# Alt_BRD_UPS_3_3V.net
KiCad netlist of a schematic drawn in Altium Designer
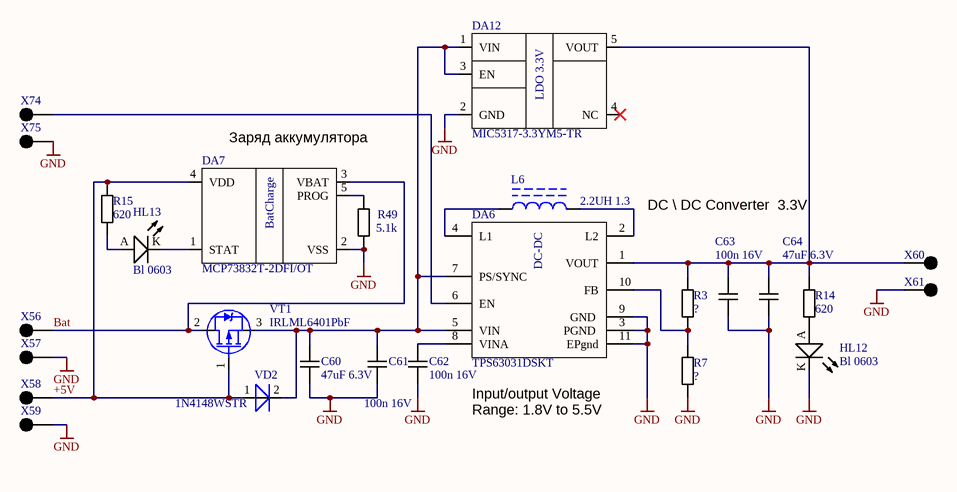
[diagram p0: Alt_BRD_UPS_3_3V.SchDoc]

(export (version "E")
  (design (tool "Eeschema 10.0.6"))
  (components
    (comp (ref "C60")
      (value "47uF 6.3V")
      (footprint "CapKemet1005(0402)")
      (description "CAP CER 47UF 6.3V X5R 0603")
      (fields
        (field (name "PART NUMBER") "GRM188R60J476ME15D")
        (field (name "DIGI-KEY PART NUMBER") "490-13247-1-ND")
      )
      (libsource (lib "SssAccesDatbase") (part "Cap"))
    )
    (comp (ref "C61")
      (value "100n 16V")
      (footprint "CapKemet1005(0402)")
      (description "Cap Cer 0.1uF 16V 1% C0G(NP0) MLCC")
      (fields
        (field (name "PART NUMBER") "CL05F104ZO5NNNC")
        (field (name "DIGI-KEY PART NUMBER") "1276-1004-1-ND")
      )
      (libsource (lib "SssAccesDatbase") (part "Cap"))
    )
    (comp (ref "C62")
      (value "100n 16V")
      (footprint "CapKemet1005(0402)")
      (description "Cap Cer 0.1uF 16V 1% C0G(NP0) MLCC")
      (fields
        (field (name "PART NUMBER") "CL05F104ZO5NNNC")
        (field (name "DIGI-KEY PART NUMBER") "1276-1004-1-ND")
      )
      (libsource (lib "SssAccesDatbase") (part "Cap"))
    )
    (comp (ref "C63")
      (value "100n 16V")
      (footprint "CapKemet1005(0402)")
      (description "Cap Cer 0.1uF 16V 1% C0G(NP0) MLCC")
      (fields
        (field (name "PART NUMBER") "CL05F104ZO5NNNC")
        (field (name "DIGI-KEY PART NUMBER") "1276-1004-1-ND")
      )
      (libsource (lib "SssAccesDatbase") (part "Cap"))
    )
    (comp (ref "C64")
      (value "47uF 6.3V")
      (footprint "CapKemet1005(0402)")
      (description "CAP CER 47UF 6.3V X5R 0603")
      (fields
        (field (name "PART NUMBER") "GRM188R60J476ME15D")
        (field (name "DIGI-KEY PART NUMBER") "490-13247-1-ND")
      )
      (libsource (lib "SssAccesDatbase") (part "Cap"))
    )
    (comp (ref "DA6")
      (value "TPS63031DSKT")
      (footprint "WSON-10")
      (description "IC REG BCK BST 3.3V 900MA 10SON")
      (fields (field (name "DIGI-KEY PART NUMBER") "296-23904-1-ND"))
      (libsource (lib "SssAccesDatbase") (part "TPS63031DSKR"))
    )
    (comp (ref "DA7")
      (value "MCP73832T-2DFI/OT")
      (footprint "SOT-23-5")
      (description "IC LI-ION/LI-POLY CTRLR SOT23-5")
      (fields (field (name "DIGI-KEY PART NUMBER") "MCP73832T-2DFI/OTCT-ND"))
      (libsource (lib "SssAccesDatbase") (part "MCP73832T-2DFI/OT"))
    )
    (comp (ref "DA12")
      (value "MIC5317-3.3YM5-TR")
      (footprint "SOT-23-OT5_N")
      (description "Linear Voltage Regulator IC 1 Output 150mA SOT-23-5")
      (fields (field (name "DIGI-KEY PART NUMBER") "MIC5317-3.3YM5-CT-ND"))
      (libsource (lib "SssAccesDatbase") (part "MIC5317-3.3YM5-TR"))
    )
    (comp (ref "HL12")
      (value "Bl 0603")
      (footprint "LED-0603-BLUE")
      (description "LED BLUE DIFFUSED 0603 SMD")
      (fields
        (field (name "PART NUMBER") "150060BS55040")
        (field (name "DIGI-KEY PART NUMBER") "732-12013-1-ND")
      )
      (libsource (lib "SssAccesDatbase") (part "LED_AK"))
    )
    (comp (ref "HL13")
      (value "Bl 0603")
      (footprint "LED-0603-BLUE")
      (description "LED BLUE DIFFUSED 0603 SMD")
      (fields
        (field (name "PART NUMBER") "150060BS55040")
        (field (name "DIGI-KEY PART NUMBER") "732-12013-1-ND")
      )
      (libsource (lib "SssAccesDatbase") (part "LED_AK"))
    )
    (comp (ref "L6")
      (value "2.2UH 1.3")
      (footprint "CDRH2D11")
      (description "FIXED IND 2.2UH 1.3A 120 MOHM")
      (fields
        (field (name "PART NUMBER") "CDRH2D11/HPNP-2R2NC")
        (field (name "DIGI-KEY PART NUMBER") "308-1578-1-ND")
        (field (name "PUBLISHER") "Altium Limited")
      )
      (libsource (lib "SssAccesDatbase") (part "Inductor ferrite"))
    )
    (comp (ref "R3")
      (value "?")
      (footprint "REZKemet 0402")
      (fields (field (name "PART NUMBER") "RESC1005(0402)"))
      (libsource (lib "SssAccesDatbase") (part "Resistor general"))
    )
    (comp (ref "R7")
      (value "?")
      (footprint "REZKemet 0402")
      (fields (field (name "PART NUMBER") "RESC1005(0402)"))
      (libsource (lib "SssAccesDatbase") (part "Resistor general"))
    )
    (comp (ref "R14")
      (value "620")
      (footprint "REZKemet 0402")
      (fields (field (name "PART NUMBER") "RESC1005(0402)"))
      (libsource (lib "SssAccesDatbase") (part "Resistor general"))
    )
    (comp (ref "R15")
      (value "620")
      (footprint "REZKemet 0402")
      (fields (field (name "PART NUMBER") "RESC1005(0402)"))
      (libsource (lib "SssAccesDatbase") (part "Resistor general"))
    )
    (comp (ref "R49")
      (value "5.1k")
      (footprint "REZKemet 0402")
      (description "RES SMD 5.1K OHM 1% 1/10W 0402")
      (fields
        (field (name "PART NUMBER") "RESC1005(0402)")
        (field (name "MANUFACTURER PART NUMBER") "ERJ-2RKF5101X")
      )
      (libsource (lib "") (part "Resistor general_1"))
    )
    (comp (ref "VD2")
      (value "1N4148WSTR")
      (footprint "SOD323")
      (description "DIODE GEN PURP 75V 300MA SOD323")
      (fields
        (field (name "DIGI-KEY PART NUMBER") "1655-1359-1-ND")
        (field (name "MANUFACTURER PART NUMBER") "?")
        (field (name "PUBLISHER") "Altium Limited")
      )
      (libsource (lib "SssAccesDatbase") (part "Diode"))
    )
    (comp (ref "VT1")
      (value "IRLML6401PbF")
      (footprint "SOT23-3N")
      (fields (field (name "DIGI-KEY PART NUMBER") "???"))
      (libsource (lib "SssAccesDatbase") (part "TRANS-P-Channel-GDS"))
    )
    (comp (ref "X56")
      (value "PLLS1.27-1-R")
      (footprint "PLLS1.27-1-R")
      (libsource (lib "SssAccesDatbase") (part "X1_1"))
    )
    (comp (ref "X57")
      (value "PLLS1.27-1-R")
      (footprint "PLLS1.27-1-R")
      (libsource (lib "SssAccesDatbase") (part "X1_1"))
    )
    (comp (ref "X58")
      (value "PLLS1.27-1-R")
      (footprint "PLLS1.27-1-R")
      (libsource (lib "SssAccesDatbase") (part "X1_1"))
    )
    (comp (ref "X59")
      (value "PLLS1.27-1-R")
      (footprint "PLLS1.27-1-R")
      (libsource (lib "SssAccesDatbase") (part "X1_1"))
    )
    (comp (ref "X60")
      (value "PLLS1.27-1-R")
      (footprint "PLLS1.27-1-R")
      (libsource (lib "SssAccesDatbase") (part "X1_1"))
    )
    (comp (ref "X61")
      (value "PLLS1.27-1-R")
      (footprint "PLLS1.27-1-R")
      (libsource (lib "SssAccesDatbase") (part "X1_1"))
    )
    (comp (ref "X74")
      (value "PLLS1.27-1-R")
      (footprint "PLLS1.27-1-R")
      (libsource (lib "SssAccesDatbase") (part "X1_1"))
    )
    (comp (ref "X75")
      (value "PLLS1.27-1-R")
      (footprint "PLLS1.27-1-R")
      (libsource (lib "SssAccesDatbase") (part "X1_1"))
    )
  )
  (nets
    (net (code "1") (name "/+5V") (class "Default")
      (node (ref "DA7") (pin "4") (pinfunction "VDD_4") (pintype "passive"))
      (node (ref "R15") (pin "2") (pinfunction "2_2") (pintype "passive"))
      (node (ref "VD2") (pin "1") (pintype "passive"))
      (node (ref "VT1") (pin "1") (pinfunction "G_1") (pintype "passive"))
      (node (ref "X58") (pin "1") (pinfunction "1_1") (pintype "passive"))
    )
    (net (code "2") (name "/Bat") (class "Default")
      (node (ref "DA7") (pin "3") (pinfunction "VBAT_3") (pintype "passive"))
      (node (ref "VT1") (pin "2") (pinfunction "D_2") (pintype "passive"))
      (node (ref "X56") (pin "1") (pinfunction "1_1") (pintype "passive"))
    )
    (net (code "3") (name "GND") (class "Default")
      (node (ref "C60") (pin "1") (pinfunction "1_1") (pintype "passive"))
      (node (ref "C61") (pin "1") (pinfunction "1_1") (pintype "passive"))
      (node (ref "C62") (pin "1") (pinfunction "1_1") (pintype "passive"))
      (node (ref "C63") (pin "1") (pinfunction "1_1") (pintype "passive"))
      (node (ref "C64") (pin "1") (pinfunction "1_1") (pintype "passive"))
      (node (ref "DA12") (pin "2") (pinfunction "GND_2") (pintype "passive"))
      (node (ref "DA6") (pin "11") (pinfunction "EPgnd_11") (pintype "passive"))
      (node (ref "DA6") (pin "3") (pinfunction "PGND_3") (pintype "passive"))
      (node (ref "DA6") (pin "9") (pinfunction "GND_9") (pintype "passive"))
      (node (ref "DA7") (pin "2") (pinfunction "VSS_2") (pintype "passive"))
      (node (ref "HL12") (pin "K") (pinfunction "K_K") (pintype "passive"))
      (node (ref "R49") (pin "2") (pinfunction "2_2") (pintype "passive"))
      (node (ref "R7") (pin "1") (pinfunction "1_1") (pintype "passive"))
      (node (ref "X57") (pin "1") (pinfunction "1_1") (pintype "passive"))
      (node (ref "X59") (pin "1") (pinfunction "1_1") (pintype "passive"))
      (node (ref "X61") (pin "1") (pinfunction "1_1") (pintype "passive"))
      (node (ref "X75") (pin "1") (pinfunction "1_1") (pintype "passive"))
    )
    (net (code "4") (name "Net-(DA6-EN)") (class "Default")
      (node (ref "DA6") (pin "6") (pinfunction "EN_6") (pintype "passive"))
      (node (ref "X74") (pin "1") (pinfunction "1_1") (pintype "passive"))
    )
    (net (code "5") (name "Net-(DA6-FB)") (class "Default")
      (node (ref "DA6") (pin "10") (pinfunction "FB_10") (pintype "passive"))
      (node (ref "R3") (pin "1") (pinfunction "1_1") (pintype "passive"))
      (node (ref "R7") (pin "2") (pinfunction "2_2") (pintype "passive"))
    )
    (net (code "6") (name "Net-(DA6-L1)") (class "Default")
      (node (ref "DA6") (pin "4") (pinfunction "L1_4") (pintype "passive"))
      (node (ref "L6") (pin "2") (pinfunction "2_2") (pintype "passive"))
    )
    (net (code "7") (name "Net-(DA6-L2)") (class "Default")
      (node (ref "DA6") (pin "2") (pinfunction "L2_2") (pintype "passive"))
      (node (ref "L6") (pin "1") (pinfunction "1_1") (pintype "passive"))
    )
    (net (code "8") (name "Net-(DA6-VINA)") (class "Default")
      (node (ref "C62") (pin "2") (pinfunction "2_2") (pintype "passive"))
      (node (ref "DA6") (pin "8") (pinfunction "VINA_8") (pintype "passive"))
    )
    (net (code "9") (name "Net-(DA7-PROG)") (class "Default")
      (node (ref "DA7") (pin "5") (pinfunction "PROG_5") (pintype "passive"))
      (node (ref "R49") (pin "1") (pinfunction "1_1") (pintype "passive"))
    )
    (net (code "10") (name "Net-(DA7-STAT)") (class "Default")
      (node (ref "DA7") (pin "1") (pinfunction "STAT_1") (pintype "passive"))
      (node (ref "HL13") (pin "K") (pinfunction "K_K") (pintype "passive"))
    )
    (net (code "11") (name "Net-(DA12-EN)") (class "Default")
      (node (ref "C60") (pin "2") (pinfunction "2_2") (pintype "passive"))
      (node (ref "C61") (pin "2") (pinfunction "2_2") (pintype "passive"))
      (node (ref "DA12") (pin "1") (pinfunction "VIN_1") (pintype "passive"))
      (node (ref "DA12") (pin "3") (pinfunction "EN_3") (pintype "passive"))
      (node (ref "DA6") (pin "5") (pinfunction "VIN_5") (pintype "passive"))
      (node (ref "DA6") (pin "7") (pinfunction "PS/SYNC_7") (pintype "passive"))
      (node (ref "VD2") (pin "2") (pintype "passive"))
      (node (ref "VT1") (pin "3") (pinfunction "S_3") (pintype "passive"))
    )
    (net (code "12") (name "Net-(DA12-VOUT)") (class "Default")
      (node (ref "C63") (pin "2") (pinfunction "2_2") (pintype "passive"))
      (node (ref "C64") (pin "2") (pinfunction "2_2") (pintype "passive"))
      (node (ref "DA12") (pin "5") (pinfunction "VOUT_5") (pintype "passive"))
      (node (ref "DA6") (pin "1") (pinfunction "VOUT_1") (pintype "passive"))
      (node (ref "R14") (pin "2") (pinfunction "2_2") (pintype "passive"))
      (node (ref "R3") (pin "2") (pinfunction "2_2") (pintype "passive"))
      (node (ref "X60") (pin "1") (pinfunction "1_1") (pintype "passive"))
    )
    (net (code "13") (name "Net-(HL12-PadA)") (class "Default")
      (node (ref "HL12") (pin "A") (pinfunction "A_A") (pintype "passive"))
      (node (ref "R14") (pin "1") (pinfunction "1_1") (pintype "passive"))
    )
    (net (code "14") (name "Net-(HL13-PadA)") (class "Default")
      (node (ref "HL13") (pin "A") (pinfunction "A_A") (pintype "passive"))
      (node (ref "R15") (pin "1") (pinfunction "1_1") (pintype "passive"))
    )
    (net (code "15") (name "unconnected-(DA12-NC-Pad4)") (class "Default")
      (node (ref "DA12") (pin "4") (pinfunction "NC_4") (pintype "passive+no_connect"))
    )
  )
)
